# connect-ino.net
KiCad netlist of a schematic drawn in EAGLE
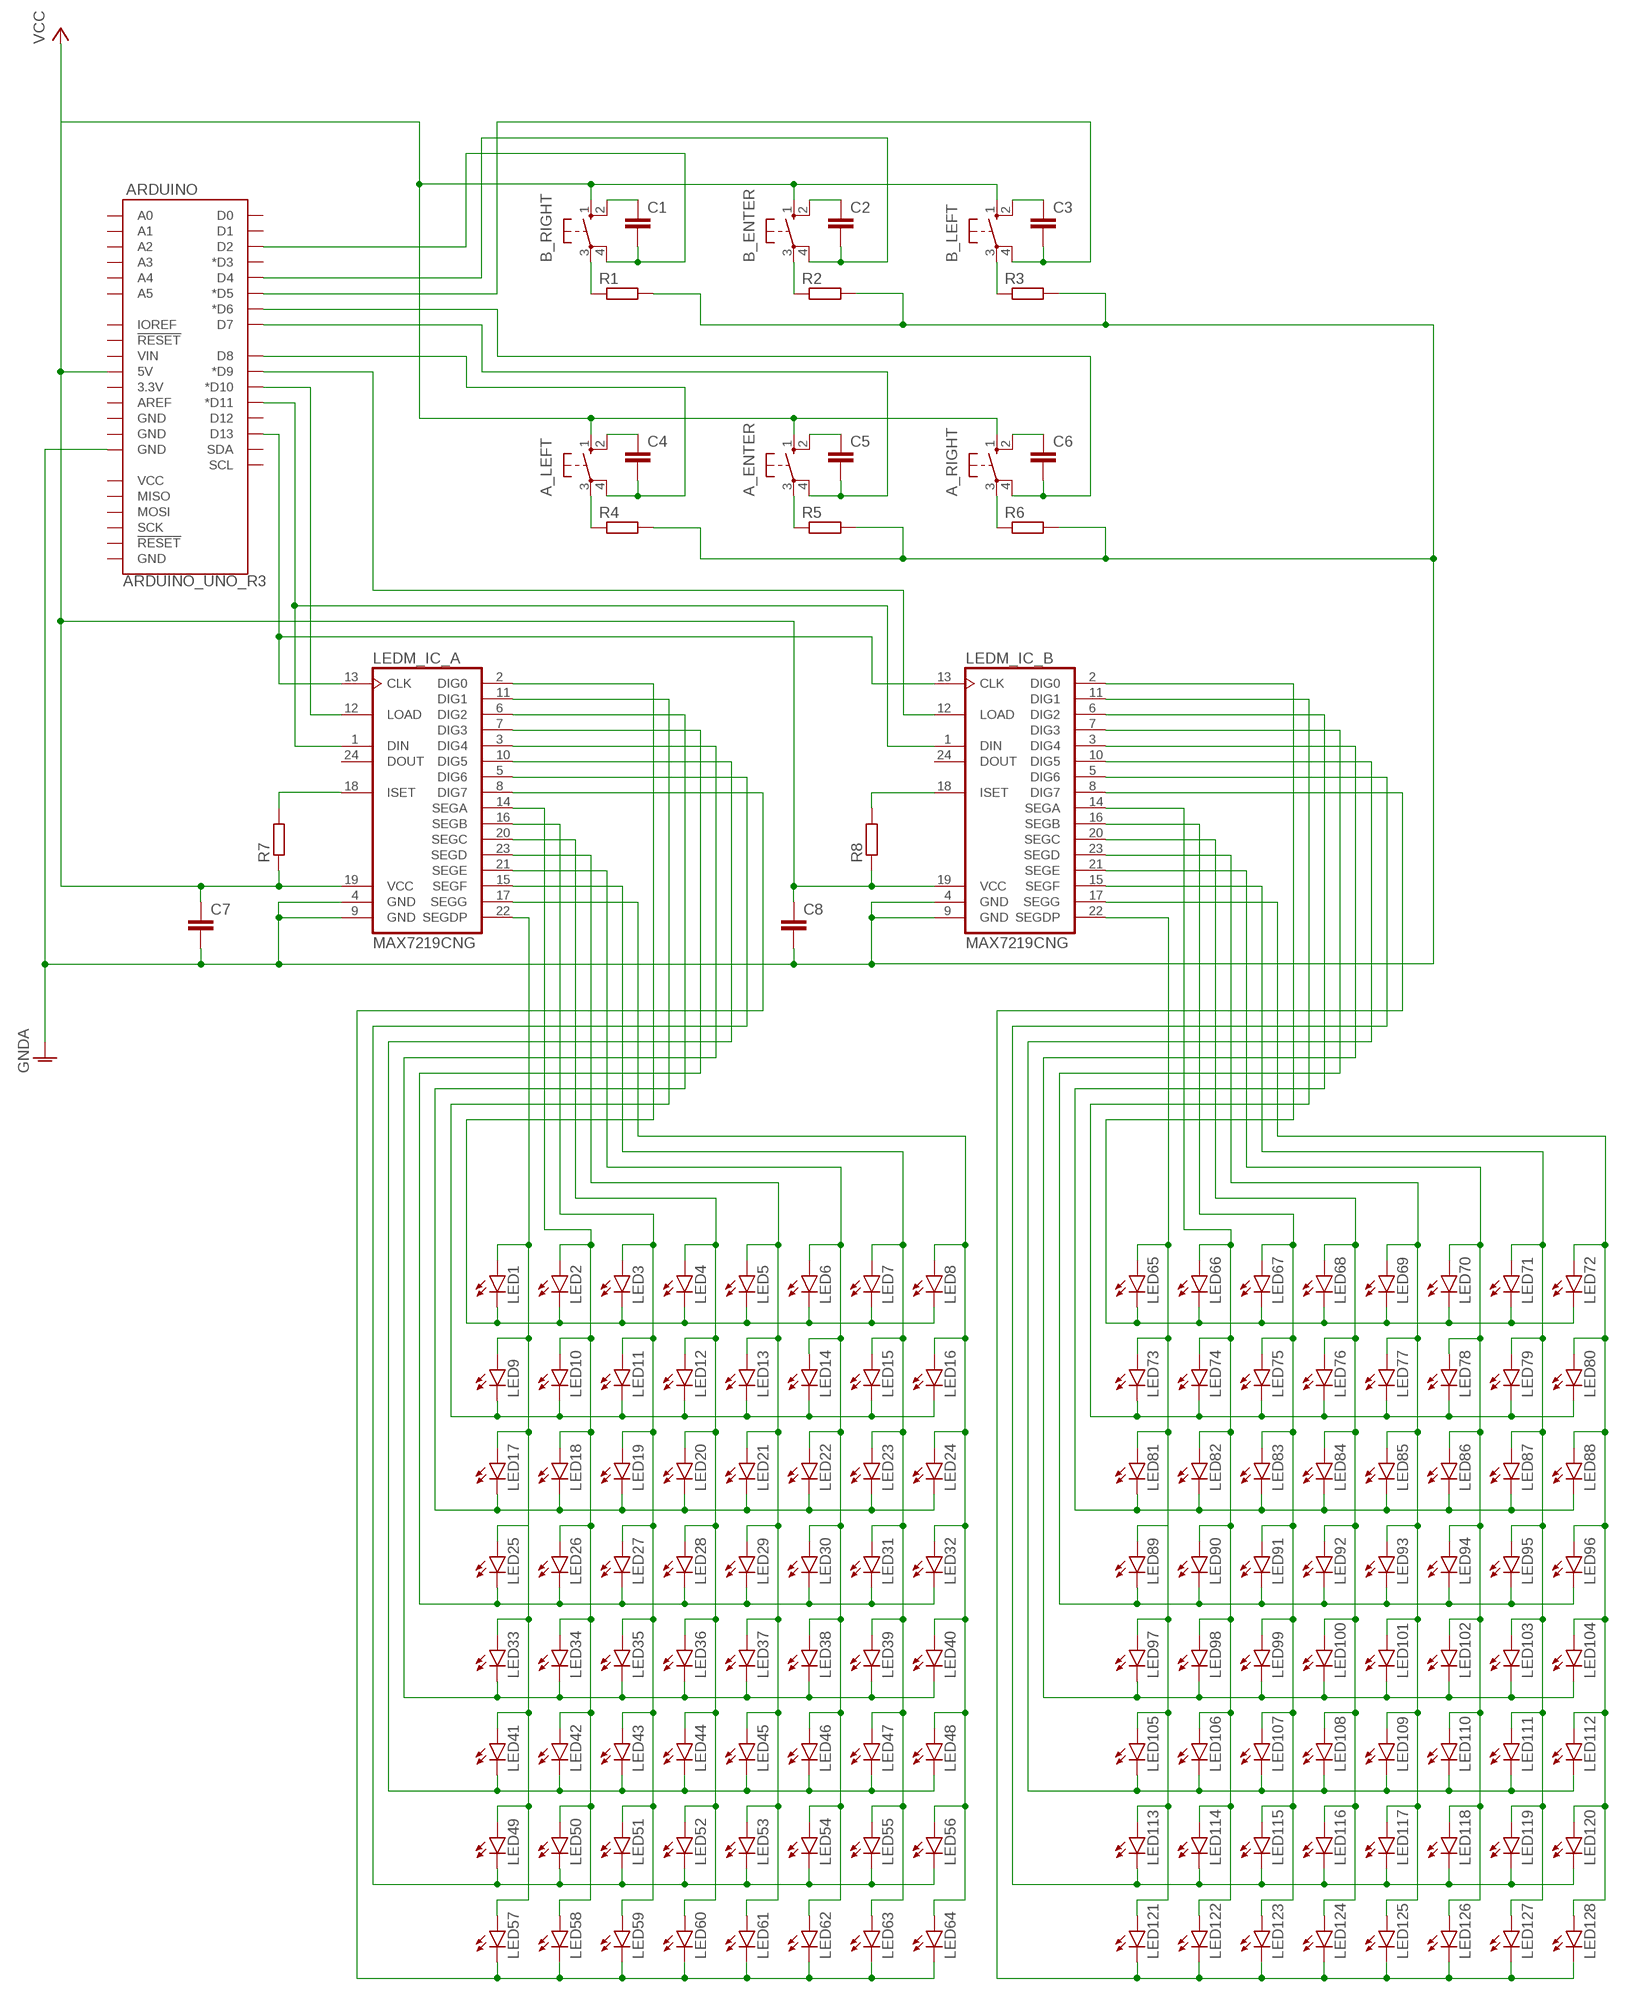
[diagram p0: schematic, sheet 1]

(export (version "E")
  (design (tool "Eeschema 10.0.6"))
  (components
    (comp (ref "ARDUINO")
      (value "ARDUINO_UNO_R3")
      (footprint "eagle-import:ARDUINO_R3")
      (libsource (lib "eagle-import") (part "ARDUINO_UNO_R3"))
    )
    (comp (ref "A_ENTER")
      (value "10-XX")
      (footprint "eagle-import:B3F-10XX")
      (fields (field (name "MPN") "B3F-1000"))
      (libsource (lib "eagle-import") (part "10-XX"))
    )
    (comp (ref "A_LEFT")
      (value "10-XX")
      (footprint "eagle-import:B3F-10XX")
      (fields (field (name "MPN") "B3F-1000"))
      (libsource (lib "eagle-import") (part "10-XX"))
    )
    (comp (ref "A_RIGHT")
      (value "10-XX")
      (footprint "eagle-import:B3F-10XX")
      (fields (field (name "MPN") "B3F-1000"))
      (libsource (lib "eagle-import") (part "10-XX"))
    )
    (comp (ref "B_ENTER")
      (value "10-XX")
      (footprint "eagle-import:B3F-10XX")
      (fields (field (name "MPN") "B3F-1000"))
      (libsource (lib "eagle-import") (part "10-XX"))
    )
    (comp (ref "B_LEFT")
      (value "10-XX")
      (footprint "eagle-import:B3F-10XX")
      (fields (field (name "MPN") "B3F-1000"))
      (libsource (lib "eagle-import") (part "10-XX"))
    )
    (comp (ref "B_RIGHT")
      (value "10-XX")
      (footprint "eagle-import:B3F-10XX")
      (fields (field (name "MPN") "B3F-1000"))
      (libsource (lib "eagle-import") (part "10-XX"))
    )
    (comp (ref "C1")
      (value "C2,5-3")
      (footprint "eagle-import:C2.5-3")
      (libsource (lib "eagle-import") (part "C2,5-3"))
    )
    (comp (ref "C2")
      (value "C2,5-3")
      (footprint "eagle-import:C2.5-3")
      (libsource (lib "eagle-import") (part "C2,5-3"))
    )
    (comp (ref "C3")
      (value "C2,5-3")
      (footprint "eagle-import:C2.5-3")
      (libsource (lib "eagle-import") (part "C2,5-3"))
    )
    (comp (ref "C4")
      (value "C2,5-3")
      (footprint "eagle-import:C2.5-3")
      (libsource (lib "eagle-import") (part "C2,5-3"))
    )
    (comp (ref "C5")
      (value "C2,5-3")
      (footprint "eagle-import:C2.5-3")
      (libsource (lib "eagle-import") (part "C2,5-3"))
    )
    (comp (ref "C6")
      (value "C2,5-3")
      (footprint "eagle-import:C2.5-3")
      (libsource (lib "eagle-import") (part "C2,5-3"))
    )
    (comp (ref "C7")
      (value "C2,5-3")
      (footprint "eagle-import:C2.5-3")
      (libsource (lib "eagle-import") (part "C2,5-3"))
    )
    (comp (ref "C8")
      (value "C2,5-3")
      (footprint "eagle-import:C2.5-3")
      (libsource (lib "eagle-import") (part "C2,5-3"))
    )
    (comp (ref "LED1")
      (value "LAP4-BOTTOM")
      (footprint "eagle-import:P47F-BOTTOM")
      (libsource (lib "eagle-import") (part "P4-BOTTOMLA"))
    )
    (comp (ref "LED2")
      (value "LAP4-BOTTOM")
      (footprint "eagle-import:P47F-BOTTOM")
      (libsource (lib "eagle-import") (part "P4-BOTTOMLA"))
    )
    (comp (ref "LED3")
      (value "LAP4-BOTTOM")
      (footprint "eagle-import:P47F-BOTTOM")
      (libsource (lib "eagle-import") (part "P4-BOTTOMLA"))
    )
    (comp (ref "LED4")
      (value "LAP4-BOTTOM")
      (footprint "eagle-import:P47F-BOTTOM")
      (libsource (lib "eagle-import") (part "P4-BOTTOMLA"))
    )
    (comp (ref "LED5")
      (value "LAP4-BOTTOM")
      (footprint "eagle-import:P47F-BOTTOM")
      (libsource (lib "eagle-import") (part "P4-BOTTOMLA"))
    )
    (comp (ref "LED6")
      (value "LAP4-BOTTOM")
      (footprint "eagle-import:P47F-BOTTOM")
      (libsource (lib "eagle-import") (part "P4-BOTTOMLA"))
    )
    (comp (ref "LED7")
      (value "LAP4-BOTTOM")
      (footprint "eagle-import:P47F-BOTTOM")
      (libsource (lib "eagle-import") (part "P4-BOTTOMLA"))
    )
    (comp (ref "LED8")
      (value "LAP4-BOTTOM")
      (footprint "eagle-import:P47F-BOTTOM")
      (libsource (lib "eagle-import") (part "P4-BOTTOMLA"))
    )
    (comp (ref "LED9")
      (value "LAP4-BOTTOM")
      (footprint "eagle-import:P47F-BOTTOM")
      (libsource (lib "eagle-import") (part "P4-BOTTOMLA"))
    )
    (comp (ref "LED10")
      (value "LAP4-BOTTOM")
      (footprint "eagle-import:P47F-BOTTOM")
      (libsource (lib "eagle-import") (part "P4-BOTTOMLA"))
    )
    (comp (ref "LED11")
      (value "LAP4-BOTTOM")
      (footprint "eagle-import:P47F-BOTTOM")
      (libsource (lib "eagle-import") (part "P4-BOTTOMLA"))
    )
    (comp (ref "LED12")
      (value "LAP4-BOTTOM")
      (footprint "eagle-import:P47F-BOTTOM")
      (libsource (lib "eagle-import") (part "P4-BOTTOMLA"))
    )
    (comp (ref "LED13")
      (value "LAP4-BOTTOM")
      (footprint "eagle-import:P47F-BOTTOM")
      (libsource (lib "eagle-import") (part "P4-BOTTOMLA"))
    )
    (comp (ref "LED14")
      (value "LAP4-BOTTOM")
      (footprint "eagle-import:P47F-BOTTOM")
      (libsource (lib "eagle-import") (part "P4-BOTTOMLA"))
    )
    (comp (ref "LED15")
      (value "LAP4-BOTTOM")
      (footprint "eagle-import:P47F-BOTTOM")
      (libsource (lib "eagle-import") (part "P4-BOTTOMLA"))
    )
    (comp (ref "LED16")
      (value "LAP4-BOTTOM")
      (footprint "eagle-import:P47F-BOTTOM")
      (libsource (lib "eagle-import") (part "P4-BOTTOMLA"))
    )
    (comp (ref "LED17")
      (value "LAP4-BOTTOM")
      (footprint "eagle-import:P47F-BOTTOM")
      (libsource (lib "eagle-import") (part "P4-BOTTOMLA"))
    )
    (comp (ref "LED18")
      (value "LAP4-BOTTOM")
      (footprint "eagle-import:P47F-BOTTOM")
      (libsource (lib "eagle-import") (part "P4-BOTTOMLA"))
    )
    (comp (ref "LED19")
      (value "LAP4-BOTTOM")
      (footprint "eagle-import:P47F-BOTTOM")
      (libsource (lib "eagle-import") (part "P4-BOTTOMLA"))
    )
    (comp (ref "LED20")
      (value "LAP4-BOTTOM")
      (footprint "eagle-import:P47F-BOTTOM")
      (libsource (lib "eagle-import") (part "P4-BOTTOMLA"))
    )
    (comp (ref "LED21")
      (value "LAP4-BOTTOM")
      (footprint "eagle-import:P47F-BOTTOM")
      (libsource (lib "eagle-import") (part "P4-BOTTOMLA"))
    )
    (comp (ref "LED22")
      (value "LAP4-BOTTOM")
      (footprint "eagle-import:P47F-BOTTOM")
      (libsource (lib "eagle-import") (part "P4-BOTTOMLA"))
    )
    (comp (ref "LED23")
      (value "LAP4-BOTTOM")
      (footprint "eagle-import:P47F-BOTTOM")
      (libsource (lib "eagle-import") (part "P4-BOTTOMLA"))
    )
    (comp (ref "LED24")
      (value "LAP4-BOTTOM")
      (footprint "eagle-import:P47F-BOTTOM")
      (libsource (lib "eagle-import") (part "P4-BOTTOMLA"))
    )
    (comp (ref "LED25")
      (value "LAP4-BOTTOM")
      (footprint "eagle-import:P47F-BOTTOM")
      (libsource (lib "eagle-import") (part "P4-BOTTOMLA"))
    )
    (comp (ref "LED26")
      (value "LAP4-BOTTOM")
      (footprint "eagle-import:P47F-BOTTOM")
      (libsource (lib "eagle-import") (part "P4-BOTTOMLA"))
    )
    (comp (ref "LED27")
      (value "LAP4-BOTTOM")
      (footprint "eagle-import:P47F-BOTTOM")
      (libsource (lib "eagle-import") (part "P4-BOTTOMLA"))
    )
    (comp (ref "LED28")
      (value "LAP4-BOTTOM")
      (footprint "eagle-import:P47F-BOTTOM")
      (libsource (lib "eagle-import") (part "P4-BOTTOMLA"))
    )
    (comp (ref "LED29")
      (value "LAP4-BOTTOM")
      (footprint "eagle-import:P47F-BOTTOM")
      (libsource (lib "eagle-import") (part "P4-BOTTOMLA"))
    )
    (comp (ref "LED30")
      (value "LAP4-BOTTOM")
      (footprint "eagle-import:P47F-BOTTOM")
      (libsource (lib "eagle-import") (part "P4-BOTTOMLA"))
    )
    (comp (ref "LED31")
      (value "LAP4-BOTTOM")
      (footprint "eagle-import:P47F-BOTTOM")
      (libsource (lib "eagle-import") (part "P4-BOTTOMLA"))
    )
    (comp (ref "LED32")
      (value "LAP4-BOTTOM")
      (footprint "eagle-import:P47F-BOTTOM")
      (libsource (lib "eagle-import") (part "P4-BOTTOMLA"))
    )
    (comp (ref "LED33")
      (value "LAP4-BOTTOM")
      (footprint "eagle-import:P47F-BOTTOM")
      (libsource (lib "eagle-import") (part "P4-BOTTOMLA"))
    )
    (comp (ref "LED34")
      (value "LAP4-BOTTOM")
      (footprint "eagle-import:P47F-BOTTOM")
      (libsource (lib "eagle-import") (part "P4-BOTTOMLA"))
    )
    (comp (ref "LED35")
      (value "LAP4-BOTTOM")
      (footprint "eagle-import:P47F-BOTTOM")
      (libsource (lib "eagle-import") (part "P4-BOTTOMLA"))
    )
    (comp (ref "LED36")
      (value "LAP4-BOTTOM")
      (footprint "eagle-import:P47F-BOTTOM")
      (libsource (lib "eagle-import") (part "P4-BOTTOMLA"))
    )
    (comp (ref "LED37")
      (value "LAP4-BOTTOM")
      (footprint "eagle-import:P47F-BOTTOM")
      (libsource (lib "eagle-import") (part "P4-BOTTOMLA"))
    )
    (comp (ref "LED38")
      (value "LAP4-BOTTOM")
      (footprint "eagle-import:P47F-BOTTOM")
      (libsource (lib "eagle-import") (part "P4-BOTTOMLA"))
    )
    (comp (ref "LED39")
      (value "LAP4-BOTTOM")
      (footprint "eagle-import:P47F-BOTTOM")
      (libsource (lib "eagle-import") (part "P4-BOTTOMLA"))
    )
    (comp (ref "LED40")
      (value "LAP4-BOTTOM")
      (footprint "eagle-import:P47F-BOTTOM")
      (libsource (lib "eagle-import") (part "P4-BOTTOMLA"))
    )
    (comp (ref "LED41")
      (value "LAP4-BOTTOM")
      (footprint "eagle-import:P47F-BOTTOM")
      (libsource (lib "eagle-import") (part "P4-BOTTOMLA"))
    )
    (comp (ref "LED42")
      (value "LAP4-BOTTOM")
      (footprint "eagle-import:P47F-BOTTOM")
      (libsource (lib "eagle-import") (part "P4-BOTTOMLA"))
    )
    (comp (ref "LED43")
      (value "LAP4-BOTTOM")
      (footprint "eagle-import:P47F-BOTTOM")
      (libsource (lib "eagle-import") (part "P4-BOTTOMLA"))
    )
    (comp (ref "LED44")
      (value "LAP4-BOTTOM")
      (footprint "eagle-import:P47F-BOTTOM")
      (libsource (lib "eagle-import") (part "P4-BOTTOMLA"))
    )
    (comp (ref "LED45")
      (value "LAP4-BOTTOM")
      (footprint "eagle-import:P47F-BOTTOM")
      (libsource (lib "eagle-import") (part "P4-BOTTOMLA"))
    )
    (comp (ref "LED46")
      (value "LAP4-BOTTOM")
      (footprint "eagle-import:P47F-BOTTOM")
      (libsource (lib "eagle-import") (part "P4-BOTTOMLA"))
    )
    (comp (ref "LED47")
      (value "LAP4-BOTTOM")
      (footprint "eagle-import:P47F-BOTTOM")
      (libsource (lib "eagle-import") (part "P4-BOTTOMLA"))
    )
    (comp (ref "LED48")
      (value "LAP4-BOTTOM")
      (footprint "eagle-import:P47F-BOTTOM")
      (libsource (lib "eagle-import") (part "P4-BOTTOMLA"))
    )
    (comp (ref "LED49")
      (value "LAP4-BOTTOM")
      (footprint "eagle-import:P47F-BOTTOM")
      (libsource (lib "eagle-import") (part "P4-BOTTOMLA"))
    )
    (comp (ref "LED50")
      (value "LAP4-BOTTOM")
      (footprint "eagle-import:P47F-BOTTOM")
      (libsource (lib "eagle-import") (part "P4-BOTTOMLA"))
    )
    (comp (ref "LED51")
      (value "LAP4-BOTTOM")
      (footprint "eagle-import:P47F-BOTTOM")
      (libsource (lib "eagle-import") (part "P4-BOTTOMLA"))
    )
    (comp (ref "LED52")
      (value "LAP4-BOTTOM")
      (footprint "eagle-import:P47F-BOTTOM")
      (libsource (lib "eagle-import") (part "P4-BOTTOMLA"))
    )
    (comp (ref "LED53")
      (value "LAP4-BOTTOM")
      (footprint "eagle-import:P47F-BOTTOM")
      (libsource (lib "eagle-import") (part "P4-BOTTOMLA"))
    )
    (comp (ref "LED54")
      (value "LAP4-BOTTOM")
      (footprint "eagle-import:P47F-BOTTOM")
      (libsource (lib "eagle-import") (part "P4-BOTTOMLA"))
    )
    (comp (ref "LED55")
      (value "LAP4-BOTTOM")
      (footprint "eagle-import:P47F-BOTTOM")
      (libsource (lib "eagle-import") (part "P4-BOTTOMLA"))
    )
    (comp (ref "LED56")
      (value "LAP4-BOTTOM")
      (footprint "eagle-import:P47F-BOTTOM")
      (libsource (lib "eagle-import") (part "P4-BOTTOMLA"))
    )
    (comp (ref "LED57")
      (value "LAP4-BOTTOM")
      (footprint "eagle-import:P47F-BOTTOM")
      (libsource (lib "eagle-import") (part "P4-BOTTOMLA"))
    )
    (comp (ref "LED58")
      (value "LAP4-BOTTOM")
      (footprint "eagle-import:P47F-BOTTOM")
      (libsource (lib "eagle-import") (part "P4-BOTTOMLA"))
    )
    (comp (ref "LED59")
      (value "LAP4-BOTTOM")
      (footprint "eagle-import:P47F-BOTTOM")
      (libsource (lib "eagle-import") (part "P4-BOTTOMLA"))
    )
    (comp (ref "LED60")
      (value "LAP4-BOTTOM")
      (footprint "eagle-import:P47F-BOTTOM")
      (libsource (lib "eagle-import") (part "P4-BOTTOMLA"))
    )
    (comp (ref "LED61")
      (value "LAP4-BOTTOM")
      (footprint "eagle-import:P47F-BOTTOM")
      (libsource (lib "eagle-import") (part "P4-BOTTOMLA"))
    )
    (comp (ref "LED62")
      (value "LAP4-BOTTOM")
      (footprint "eagle-import:P47F-BOTTOM")
      (libsource (lib "eagle-import") (part "P4-BOTTOMLA"))
    )
    (comp (ref "LED63")
      (value "LAP4-BOTTOM")
      (footprint "eagle-import:P47F-BOTTOM")
      (libsource (lib "eagle-import") (part "P4-BOTTOMLA"))
    )
    (comp (ref "LED64")
      (value "LAP4-BOTTOM")
      (footprint "eagle-import:P47F-BOTTOM")
      (libsource (lib "eagle-import") (part "P4-BOTTOMLA"))
    )
    (comp (ref "LED65")
      (value "LAP4-BOTTOM")
      (footprint "eagle-import:P47F-BOTTOM")
      (libsource (lib "eagle-import") (part "P4-BOTTOMLA"))
    )
    (comp (ref "LED66")
      (value "LAP4-BOTTOM")
      (footprint "eagle-import:P47F-BOTTOM")
      (libsource (lib "eagle-import") (part "P4-BOTTOMLA"))
    )
    (comp (ref "LED67")
      (value "LAP4-BOTTOM")
      (footprint "eagle-import:P47F-BOTTOM")
      (libsource (lib "eagle-import") (part "P4-BOTTOMLA"))
    )
    (comp (ref "LED68")
      (value "LAP4-BOTTOM")
      (footprint "eagle-import:P47F-BOTTOM")
      (libsource (lib "eagle-import") (part "P4-BOTTOMLA"))
    )
    (comp (ref "LED69")
      (value "LAP4-BOTTOM")
      (footprint "eagle-import:P47F-BOTTOM")
      (libsource (lib "eagle-import") (part "P4-BOTTOMLA"))
    )
    (comp (ref "LED70")
      (value "LAP4-BOTTOM")
      (footprint "eagle-import:P47F-BOTTOM")
      (libsource (lib "eagle-import") (part "P4-BOTTOMLA"))
    )
    (comp (ref "LED71")
      (value "LAP4-BOTTOM")
      (footprint "eagle-import:P47F-BOTTOM")
      (libsource (lib "eagle-import") (part "P4-BOTTOMLA"))
    )
    (comp (ref "LED72")
      (value "LAP4-BOTTOM")
      (footprint "eagle-import:P47F-BOTTOM")
      (libsource (lib "eagle-import") (part "P4-BOTTOMLA"))
    )
    (comp (ref "LED73")
      (value "LAP4-BOTTOM")
      (footprint "eagle-import:P47F-BOTTOM")
      (libsource (lib "eagle-import") (part "P4-BOTTOMLA"))
    )
    (comp (ref "LED74")
      (value "LAP4-BOTTOM")
      (footprint "eagle-import:P47F-BOTTOM")
      (libsource (lib "eagle-import") (part "P4-BOTTOMLA"))
    )
    (comp (ref "LED75")
      (value "LAP4-BOTTOM")
      (footprint "eagle-import:P47F-BOTTOM")
      (libsource (lib "eagle-import") (part "P4-BOTTOMLA"))
    )
    (comp (ref "LED76")
      (value "LAP4-BOTTOM")
      (footprint "eagle-import:P47F-BOTTOM")
      (libsource (lib "eagle-import") (part "P4-BOTTOMLA"))
    )
    (comp (ref "LED77")
      (value "LAP4-BOTTOM")
      (footprint "eagle-import:P47F-BOTTOM")
      (libsource (lib "eagle-import") (part "P4-BOTTOMLA"))
    )
    (comp (ref "LED78")
      (value "LAP4-BOTTOM")
      (footprint "eagle-import:P47F-BOTTOM")
      (libsource (lib "eagle-import") (part "P4-BOTTOMLA"))
    )
    (comp (ref "LED79")
      (value "LAP4-BOTTOM")
      (footprint "eagle-import:P47F-BOTTOM")
      (libsource (lib "eagle-import") (part "P4-BOTTOMLA"))
    )
    (comp (ref "LED80")
      (value "LAP4-BOTTOM")
      (footprint "eagle-import:P47F-BOTTOM")
      (libsource (lib "eagle-import") (part "P4-BOTTOMLA"))
    )
    (comp (ref "LED81")
      (value "LAP4-BOTTOM")
      (footprint "eagle-import:P47F-BOTTOM")
      (libsource (lib "eagle-import") (part "P4-BOTTOMLA"))
    )
    (comp (ref "LED82")
      (value "LAP4-BOTTOM")
      (footprint "eagle-import:P47F-BOTTOM")
      (libsource (lib "eagle-import") (part "P4-BOTTOMLA"))
    )
    (comp (ref "LED83")
      (value "LAP4-BOTTOM")
      (footprint "eagle-import:P47F-BOTTOM")
      (libsource (lib "eagle-import") (part "P4-BOTTOMLA"))
    )
    (comp (ref "LED84")
      (value "LAP4-BOTTOM")
      (footprint "eagle-import:P47F-BOTTOM")
      (libsource (lib "eagle-import") (part "P4-BOTTOMLA"))
    )
    (comp (ref "LED85")
      (value "LAP4-BOTTOM")
      (footprint "eagle-import:P47F-BOTTOM")
      (libsource (lib "eagle-import") (part "P4-BOTTOMLA"))
    )
    (comp (ref "LED86")
      (value "LAP4-BOTTOM")
      (footprint "eagle-import:P47F-BOTTOM")
      (libsource (lib "eagle-import") (part "P4-BOTTOMLA"))
    )
    (comp (ref "LED87")
      (value "LAP4-BOTTOM")
      (footprint "eagle-import:P47F-BOTTOM")
      (libsource (lib "eagle-import") (part "P4-BOTTOMLA"))
    )
    (comp (ref "LED88")
      (value "LAP4-BOTTOM")
      (footprint "eagle-import:P47F-BOTTOM")
      (libsource (lib "eagle-import") (part "P4-BOTTOMLA"))
    )
    (comp (ref "LED89")
      (value "LAP4-BOTTOM")
      (footprint "eagle-import:P47F-BOTTOM")
      (libsource (lib "eagle-import") (part "P4-BOTTOMLA"))
    )
    (comp (ref "LED90")
      (value "LAP4-BOTTOM")
      (footprint "eagle-import:P47F-BOTTOM")
      (libsource (lib "eagle-import") (part "P4-BOTTOMLA"))
    )
    (comp (ref "LED91")
      (value "LAP4-BOTTOM")
      (footprint "eagle-import:P47F-BOTTOM")
      (libsource (lib "eagle-import") (part "P4-BOTTOMLA"))
    )
    (comp (ref "LED92")
      (value "LAP4-BOTTOM")
      (footprint "eagle-import:P47F-BOTTOM")
      (libsource (lib "eagle-import") (part "P4-BOTTOMLA"))
    )
    (comp (ref "LED93")
      (value "LAP4-BOTTOM")
      (footprint "eagle-import:P47F-BOTTOM")
      (libsource (lib "eagle-import") (part "P4-BOTTOMLA"))
    )
    (comp (ref "LED94")
      (value "LAP4-BOTTOM")
      (footprint "eagle-import:P47F-BOTTOM")
      (libsource (lib "eagle-import") (part "P4-BOTTOMLA"))
    )
    (comp (ref "LED95")
      (value "LAP4-BOTTOM")
      (footprint "eagle-import:P47F-BOTTOM")
      (libsource (lib "eagle-import") (part "P4-BOTTOMLA"))
    )
    (comp (ref "LED96")
      (value "LAP4-BOTTOM")
      (footprint "eagle-import:P47F-BOTTOM")
      (libsource (lib "eagle-import") (part "P4-BOTTOMLA"))
    )
    (comp (ref "LED97")
      (value "LAP4-BOTTOM")
      (footprint "eagle-import:P47F-BOTTOM")
      (libsource (lib "eagle-import") (part "P4-BOTTOMLA"))
    )
    (comp (ref "LED98")
      (value "LAP4-BOTTOM")
      (footprint "eagle-import:P47F-BOTTOM")
      (libsource (lib "eagle-import") (part "P4-BOTTOMLA"))
    )
    (comp (ref "LED99")
      (value "LAP4-BOTTOM")
      (footprint "eagle-import:P47F-BOTTOM")
      (libsource (lib "eagle-import") (part "P4-BOTTOMLA"))
    )
    (comp (ref "LED100")
      (value "LAP4-BOTTOM")
      (footprint "eagle-import:P47F-BOTTOM")
      (libsource (lib "eagle-import") (part "P4-BOTTOMLA"))
    )
    (comp (ref "LED101")
      (value "LAP4-BOTTOM")
      (footprint "eagle-import:P47F-BOTTOM")
      (libsource (lib "eagle-import") (part "P4-BOTTOMLA"))
    )
    (comp (ref "LED102")
      (value "LAP4-BOTTOM")
      (footprint "eagle-import:P47F-BOTTOM")
      (libsource (lib "eagle-import") (part "P4-BOTTOMLA"))
    )
    (comp (ref "LED103")
      (value "LAP4-BOTTOM")
      (footprint "eagle-import:P47F-BOTTOM")
      (libsource (lib "eagle-import") (part "P4-BOTTOMLA"))
    )
    (comp (ref "LED104")
      (value "LAP4-BOTTOM")
      (footprint "eagle-import:P47F-BOTTOM")
      (libsource (lib "eagle-import") (part "P4-BOTTOMLA"))
    )
    (comp (ref "LED105")
      (value "LAP4-BOTTOM")
      (footprint "eagle-import:P47F-BOTTOM")
      (libsource (lib "eagle-import") (part "P4-BOTTOMLA"))
    )
    (comp (ref "LED106")
      (value "LAP4-BOTTOM")
      (footprint "eagle-import:P47F-BOTTOM")
      (libsource (lib "eagle-import") (part "P4-BOTTOMLA"))
    )
    (comp (ref "LED107")
      (value "LAP4-BOTTOM")
      (footprint "eagle-import:P47F-BOTTOM")
      (libsource (lib "eagle-import") (part "P4-BOTTOMLA"))
    )
    (comp (ref "LED108")
      (value "LAP4-BOTTOM")
      (footprint "eagle-import:P47F-BOTTOM")
      (libsource (lib "eagle-import") (part "P4-BOTTOMLA"))
    )
    (comp (ref "LED109")
      (value "LAP4-BOTTOM")
      (footprint "eagle-import:P47F-BOTTOM")
      (libsource (lib "eagle-import") (part "P4-BOTTOMLA"))
    )
    (comp (ref "LED110")
      (value "LAP4-BOTTOM")
      (footprint "eagle-import:P47F-BOTTOM")
      (libsource (lib "eagle-import") (part "P4-BOTTOMLA"))
    )
    (comp (ref "LED111")
      (value "LAP4-BOTTOM")
      (footprint "eagle-import:P47F-BOTTOM")
      (libsource (lib "eagle-import") (part "P4-BOTTOMLA"))
    )
    (comp (ref "LED112")
      (value "LAP4-BOTTOM")
      (footprint "eagle-import:P47F-BOTTOM")
      (libsource (lib "eagle-import") (part "P4-BOTTOMLA"))
    )
    (comp (ref "LED113")
      (value "LAP4-BOTTOM")
      (footprint "eagle-import:P47F-BOTTOM")
      (libsource (lib "eagle-import") (part "P4-BOTTOMLA"))
    )
    (comp (ref "LED114")
      (value "LAP4-BOTTOM")
      (footprint "eagle-import:P47F-BOTTOM")
      (libsource (lib "eagle-import") (part "P4-BOTTOMLA"))
    )
    (comp (ref "LED115")
      (value "LAP4-BOTTOM")
      (footprint "eagle-import:P47F-BOTTOM")
      (libsource (lib "eagle-import") (part "P4-BOTTOMLA"))
    )
    (comp (ref "LED116")
      (value "LAP4-BOTTOM")
      (footprint "eagle-import:P47F-BOTTOM")
      (libsource (lib "eagle-import") (part "P4-BOTTOMLA"))
    )
    (comp (ref "LED117")
      (value "LAP4-BOTTOM")
      (footprint "eagle-import:P47F-BOTTOM")
      (libsource (lib "eagle-import") (part "P4-BOTTOMLA"))
    )
    (comp (ref "LED118")
      (value "LAP4-BOTTOM")
      (footprint "eagle-import:P47F-BOTTOM")
      (libsource (lib "eagle-import") (part "P4-BOTTOMLA"))
    )
    (comp (ref "LED119")
      (value "LAP4-BOTTOM")
      (footprint "eagle-import:P47F-BOTTOM")
      (libsource (lib "eagle-import") (part "P4-BOTTOMLA"))
    )
    (comp (ref "LED120")
      (value "LAP4-BOTTOM")
      (footprint "eagle-import:P47F-BOTTOM")
      (libsource (lib "eagle-import") (part "P4-BOTTOMLA"))
    )
    (comp (ref "LED121")
      (value "LAP4-BOTTOM")
      (footprint "eagle-import:P47F-BOTTOM")
      (libsource (lib "eagle-import") (part "P4-BOTTOMLA"))
    )
    (comp (ref "LED122")
      (value "LAP4-BOTTOM")
      (footprint "eagle-import:P47F-BOTTOM")
      (libsource (lib "eagle-import") (part "P4-BOTTOMLA"))
    )
    (comp (ref "LED123")
      (value "LAP4-BOTTOM")
      (footprint "eagle-import:P47F-BOTTOM")
      (libsource (lib "eagle-import") (part "P4-BOTTOMLA"))
    )
    (comp (ref "LED124")
      (value "LAP4-BOTTOM")
      (footprint "eagle-import:P47F-BOTTOM")
      (libsource (lib "eagle-import") (part "P4-BOTTOMLA"))
    )
    (comp (ref "LED125")
      (value "LAP4-BOTTOM")
      (footprint "eagle-import:P47F-BOTTOM")
      (libsource (lib "eagle-import") (part "P4-BOTTOMLA"))
    )
    (comp (ref "LED126")
      (value "LAP4-BOTTOM")
      (footprint "eagle-import:P47F-BOTTOM")
      (libsource (lib "eagle-import") (part "P4-BOTTOMLA"))
    )
    (comp (ref "LED127")
      (value "LAP4-BOTTOM")
      (footprint "eagle-import:P47F-BOTTOM")
      (libsource (lib "eagle-import") (part "P4-BOTTOMLA"))
    )
    (comp (ref "LED128")
      (value "LAP4-BOTTOM")
      (footprint "eagle-import:P47F-BOTTOM")
      (libsource (lib "eagle-import") (part "P4-BOTTOMLA"))
    )
    (comp (ref "LEDM_IC_A")
      (value "MAX7219CNG")
      (footprint "eagle-import:DIL24-3")
      (fields (field (name "MF") "MAXIM"))
      (libsource (lib "eagle-import") (part "MAX7219CNG"))
    )
    (comp (ref "LEDM_IC_B")
      (value "MAX7219CNG")
      (footprint "eagle-import:DIL24-3")
      (fields (field (name "MF") "MAXIM"))
      (libsource (lib "eagle-import") (part "MAX7219CNG"))
    )
    (comp (ref "R1")
      (value "R-EU_0204/2V")
      (footprint "eagle-import:0204V")
      (libsource (lib "eagle-import") (part "R-EU_0204/2V"))
    )
    (comp (ref "R2")
      (value "R-EU_0204/2V")
      (footprint "eagle-import:0204V")
      (libsource (lib "eagle-import") (part "R-EU_0204/2V"))
    )
    (comp (ref "R3")
      (value "R-EU_0204/2V")
      (footprint "eagle-import:0204V")
      (libsource (lib "eagle-import") (part "R-EU_0204/2V"))
    )
    (comp (ref "R4")
      (value "R-EU_0204/2V")
      (footprint "eagle-import:0204V")
      (libsource (lib "eagle-import") (part "R-EU_0204/2V"))
    )
    (comp (ref "R5")
      (value "R-EU_0204/2V")
      (footprint "eagle-import:0204V")
      (libsource (lib "eagle-import") (part "R-EU_0204/2V"))
    )
    (comp (ref "R6")
      (value "R-EU_0204/2V")
      (footprint "eagle-import:0204V")
      (libsource (lib "eagle-import") (part "R-EU_0204/2V"))
    )
    (comp (ref "R7")
      (value "R-EU_0204/2V")
      (footprint "eagle-import:0204V")
      (libsource (lib "eagle-import") (part "R-EU_0204/2V"))
    )
    (comp (ref "R8")
      (value "R-EU_0204/2V")
      (footprint "eagle-import:0204V")
      (libsource (lib "eagle-import") (part "R-EU_0204/2V"))
    )
  )
  (nets
    (net (code "1") (name "GNDA") (class "Default")
      (node (ref "ARDUINO") (pin "GND@2") (pinfunction "GND_GND@2") (pintype "bidirectional"))
      (node (ref "C7") (pin "2") (pinfunction "2_2") (pintype "passive"))
      (node (ref "C8") (pin "2") (pinfunction "2_2") (pintype "passive"))
      (node (ref "LEDM_IC_A") (pin "4") (pinfunction "GND_4") (pintype "power_in"))
      (node (ref "LEDM_IC_A") (pin "9") (pinfunction "GND_9") (pintype "power_in"))
      (node (ref "LEDM_IC_B") (pin "4") (pinfunction "GND_4") (pintype "power_in"))
      (node (ref "LEDM_IC_B") (pin "9") (pinfunction "GND_9") (pintype "power_in"))
      (node (ref "R1") (pin "2") (pinfunction "2_2") (pintype "passive"))
      (node (ref "R2") (pin "2") (pinfunction "2_2") (pintype "passive"))
      (node (ref "R3") (pin "2") (pinfunction "2_2") (pintype "passive"))
      (node (ref "R4") (pin "2") (pinfunction "2_2") (pintype "passive"))
      (node (ref "R5") (pin "2") (pinfunction "2_2") (pintype "passive"))
      (node (ref "R6") (pin "2") (pinfunction "2_2") (pintype "passive"))
    )
    (net (code "2") (name "Net-(ARDUINO-*D5)") (class "Default")
      (node (ref "ARDUINO") (pin "D5") (pinfunction "*D5_D5") (pintype "bidirectional"))
      (node (ref "B_LEFT") (pin "4") (pinfunction "P1_4") (pintype "passive"))
      (node (ref "C3") (pin "2") (pinfunction "2_2") (pintype "passive"))
    )
    (net (code "3") (name "Net-(ARDUINO-*D6)") (class "Default")
      (node (ref "ARDUINO") (pin "D6") (pinfunction "*D6_D6") (pintype "bidirectional"))
      (node (ref "A_RIGHT") (pin "4") (pinfunction "P1_4") (pintype "passive"))
      (node (ref "C6") (pin "2") (pinfunction "2_2") (pintype "passive"))
    )
    (net (code "4") (name "Net-(ARDUINO-*D9)") (class "Default")
      (node (ref "ARDUINO") (pin "D9") (pinfunction "*D9_D9") (pintype "bidirectional"))
      (node (ref "LEDM_IC_B") (pin "12") (pinfunction "LOAD_12") (pintype "input"))
    )
    (net (code "5") (name "Net-(ARDUINO-*D10)") (class "Default")
      (node (ref "ARDUINO") (pin "D10") (pinfunction "*D10_D10") (pintype "bidirectional"))
      (node (ref "LEDM_IC_A") (pin "12") (pinfunction "LOAD_12") (pintype "input"))
    )
    (net (code "6") (name "Net-(ARDUINO-*D11)") (class "Default")
      (node (ref "ARDUINO") (pin "D11") (pinfunction "*D11_D11") (pintype "bidirectional"))
      (node (ref "LEDM_IC_A") (pin "1") (pinfunction "DIN_1") (pintype "input"))
      (node (ref "LEDM_IC_B") (pin "1") (pinfunction "DIN_1") (pintype "input"))
    )
    (net (code "7") (name "Net-(A_ENTER-P)") (class "Default")
      (node (ref "A_ENTER") (pin "3") (pinfunction "P_3") (pintype "passive"))
      (node (ref "R5") (pin "1") (pinfunction "1_1") (pintype "passive"))
    )
    (net (code "8") (name "Net-(A_ENTER-P1)") (class "Default")
      (node (ref "ARDUINO") (pin "D7") (pinfunction "D7_D7") (pintype "bidirectional"))
      (node (ref "A_ENTER") (pin "4") (pinfunction "P1_4") (pintype "passive"))
      (node (ref "C5") (pin "2") (pinfunction "2_2") (pintype "passive"))
    )
    (net (code "9") (name "Net-(A_ENTER-S1)") (class "Default")
      (node (ref "A_ENTER") (pin "2") (pinfunction "S1_2") (pintype "passive"))
      (node (ref "C5") (pin "1") (pinfunction "1_1") (pintype "passive"))
    )
    (net (code "10") (name "Net-(A_LEFT-P)") (class "Default")
      (node (ref "A_LEFT") (pin "3") (pinfunction "P_3") (pintype "passive"))
      (node (ref "R4") (pin "1") (pinfunction "1_1") (pintype "passive"))
    )
    (net (code "11") (name "Net-(A_LEFT-P1)") (class "Default")
      (node (ref "ARDUINO") (pin "D8") (pinfunction "D8_D8") (pintype "bidirectional"))
      (node (ref "A_LEFT") (pin "4") (pinfunction "P1_4") (pintype "passive"))
      (node (ref "C4") (pin "2") (pinfunction "2_2") (pintype "passive"))
    )
    (net (code "12") (name "Net-(A_LEFT-S1)") (class "Default")
      (node (ref "A_LEFT") (pin "2") (pinfunction "S1_2") (pintype "passive"))
      (node (ref "C4") (pin "1") (pinfunction "1_1") (pintype "passive"))
    )
    (net (code "13") (name "Net-(A_RIGHT-P)") (class "Default")
      (node (ref "A_RIGHT") (pin "3") (pinfunction "P_3") (pintype "passive"))
      (node (ref "R6") (pin "1") (pinfunction "1_1") (pintype "passive"))
    )
    (net (code "14") (name "Net-(A_RIGHT-S1)") (class "Default")
      (node (ref "A_RIGHT") (pin "2") (pinfunction "S1_2") (pintype "passive"))
      (node (ref "C6") (pin "1") (pinfunction "1_1") (pintype "passive"))
    )
    (net (code "15") (name "Net-(B_ENTER-P)") (class "Default")
      (node (ref "B_ENTER") (pin "3") (pinfunction "P_3") (pintype "passive"))
      (node (ref "R2") (pin "1") (pinfunction "1_1") (pintype "passive"))
    )
    (net (code "16") (name "Net-(B_ENTER-P1)") (class "Default")
      (node (ref "ARDUINO") (pin "D4") (pinfunction "D4_D4") (pintype "bidirectional"))
      (node (ref "B_ENTER") (pin "4") (pinfunction "P1_4") (pintype "passive"))
      (node (ref "C2") (pin "2") (pinfunction "2_2") (pintype "passive"))
    )
    (net (code "17") (name "Net-(B_ENTER-S1)") (class "Default")
      (node (ref "B_ENTER") (pin "2") (pinfunction "S1_2") (pintype "passive"))
      (node (ref "C2") (pin "1") (pinfunction "1_1") (pintype "passive"))
    )
    (net (code "18") (name "Net-(B_LEFT-P)") (class "Default")
      (node (ref "B_LEFT") (pin "3") (pinfunction "P_3") (pintype "passive"))
      (node (ref "R3") (pin "1") (pinfunction "1_1") (pintype "passive"))
    )
    (net (code "19") (name "Net-(B_LEFT-S1)") (class "Default")
      (node (ref "B_LEFT") (pin "2") (pinfunction "S1_2") (pintype "passive"))
      (node (ref "C3") (pin "1") (pinfunction "1_1") (pintype "passive"))
    )
    (net (code "20") (name "Net-(B_RIGHT-P)") (class "Default")
      (node (ref "B_RIGHT") (pin "3") (pinfunction "P_3") (pintype "passive"))
      (node (ref "R1") (pin "1") (pinfunction "1_1") (pintype "passive"))
    )
    (net (code "21") (name "Net-(B_RIGHT-P1)") (class "Default")
      (node (ref "ARDUINO") (pin "D2") (pinfunction "D2_D2") (pintype "bidirectional"))
      (node (ref "B_RIGHT") (pin "4") (pinfunction "P1_4") (pintype "passive"))
      (node (ref "C1") (pin "2") (pinfunction "2_2") (pintype "passive"))
    )
    (net (code "22") (name "Net-(B_RIGHT-S1)") (class "Default")
      (node (ref "B_RIGHT") (pin "2") (pinfunction "S1_2") (pintype "passive"))
      (node (ref "C1") (pin "1") (pinfunction "1_1") (pintype "passive"))
    )
    (net (code "23") (name "Net-(LEDM_IC_A-CLK)") (class "Default")
      (node (ref "ARDUINO") (pin "D13") (pinfunction "D13_D13") (pintype "bidirectional"))
      (node (ref "LEDM_IC_A") (pin "13") (pinfunction "CLK_13") (pintype "input"))
      (node (ref "LEDM_IC_B") (pin "13") (pinfunction "CLK_13") (pintype "input"))
    )
    (net (code "24") (name "Net-(LEDM_IC_A-DIG0)") (class "Default")
      (node (ref "LED1") (pin "C") (pinfunction "C_C") (pintype "passive"))
      (node (ref "LED2") (pin "C") (pinfunction "C_C") (pintype "passive"))
      (node (ref "LED3") (pin "C") (pinfunction "C_C") (pintype "passive"))
      (node (ref "LED4") (pin "C") (pinfunction "C_C") (pintype "passive"))
      (node (ref "LED5") (pin "C") (pinfunction "C_C") (pintype "passive"))
      (node (ref "LED6") (pin "C") (pinfunction "C_C") (pintype "passive"))
      (node (ref "LED7") (pin "C") (pinfunction "C_C") (pintype "passive"))
      (node (ref "LED8") (pin "C") (pinfunction "C_C") (pintype "passive"))
      (node (ref "LEDM_IC_A") (pin "2") (pinfunction "DIG0_2") (pintype "output"))
    )
    (net (code "25") (name "Net-(LEDM_IC_A-DIG1)") (class "Default")
      (node (ref "LED10") (pin "C") (pinfunction "C_C") (pintype "passive"))
      (node (ref "LED11") (pin "C") (pinfunction "C_C") (pintype "passive"))
      (node (ref "LED12") (pin "C") (pinfunction "C_C") (pintype "passive"))
      (node (ref "LED13") (pin "C") (pinfunction "C_C") (pintype "passive"))
      (node (ref "LED14") (pin "C") (pinfunction "C_C") (pintype "passive"))
      (node (ref "LED15") (pin "C") (pinfunction "C_C") (pintype "passive"))
      (node (ref "LED16") (pin "C") (pinfunction "C_C") (pintype "passive"))
      (node (ref "LED9") (pin "C") (pinfunction "C_C") (pintype "passive"))
      (node (ref "LEDM_IC_A") (pin "11") (pinfunction "DIG1_11") (pintype "output"))
    )
    (net (code "26") (name "Net-(LEDM_IC_A-DIG2)") (class "Default")
      (node (ref "LED17") (pin "C") (pinfunction "C_C") (pintype "passive"))
      (node (ref "LED18") (pin "C") (pinfunction "C_C") (pintype "passive"))
      (node (ref "LED19") (pin "C") (pinfunction "C_C") (pintype "passive"))
      (node (ref "LED20") (pin "C") (pinfunction "C_C") (pintype "passive"))
      (node (ref "LED21") (pin "C") (pinfunction "C_C") (pintype "passive"))
      (node (ref "LED22") (pin "C") (pinfunction "C_C") (pintype "passive"))
      (node (ref "LED23") (pin "C") (pinfunction "C_C") (pintype "passive"))
      (node (ref "LED24") (pin "C") (pinfunction "C_C") (pintype "passive"))
      (node (ref "LEDM_IC_A") (pin "6") (pinfunction "DIG2_6") (pintype "output"))
    )
    (net (code "27") (name "Net-(LEDM_IC_A-DIG3)") (class "Default")
      (node (ref "LED25") (pin "C") (pinfunction "C_C") (pintype "passive"))
      (node (ref "LED26") (pin "C") (pinfunction "C_C") (pintype "passive"))
      (node (ref "LED27") (pin "C") (pinfunction "C_C") (pintype "passive"))
      (node (ref "LED28") (pin "C") (pinfunction "C_C") (pintype "passive"))
      (node (ref "LED29") (pin "C") (pinfunction "C_C") (pintype "passive"))
      (node (ref "LED30") (pin "C") (pinfunction "C_C") (pintype "passive"))
      (node (ref "LED31") (pin "C") (pinfunction "C_C") (pintype "passive"))
      (node (ref "LED32") (pin "C") (pinfunction "C_C") (pintype "passive"))
      (node (ref "LEDM_IC_A") (pin "7") (pinfunction "DIG3_7") (pintype "output"))
    )
    (net (code "28") (name "Net-(LEDM_IC_A-DIG4)") (class "Default")
      (node (ref "LED33") (pin "C") (pinfunction "C_C") (pintype "passive"))
      (node (ref "LED34") (pin "C") (pinfunction "C_C") (pintype "passive"))
      (node (ref "LED35") (pin "C") (pinfunction "C_C") (pintype "passive"))
      (node (ref "LED36") (pin "C") (pinfunction "C_C") (pintype "passive"))
      (node (ref "LED37") (pin "C") (pinfunction "C_C") (pintype "passive"))
      (node (ref "LED38") (pin "C") (pinfunction "C_C") (pintype "passive"))
      (node (ref "LED39") (pin "C") (pinfunction "C_C") (pintype "passive"))
      (node (ref "LED40") (pin "C") (pinfunction "C_C") (pintype "passive"))
      (node (ref "LEDM_IC_A") (pin "3") (pinfunction "DIG4_3") (pintype "output"))
    )
    (net (code "29") (name "Net-(LEDM_IC_A-DIG5)") (class "Default")
      (node (ref "LED41") (pin "C") (pinfunction "C_C") (pintype "passive"))
      (node (ref "LED42") (pin "C") (pinfunction "C_C") (pintype "passive"))
      (node (ref "LED43") (pin "C") (pinfunction "C_C") (pintype "passive"))
      (node (ref "LED44") (pin "C") (pinfunction "C_C") (pintype "passive"))
      (node (ref "LED45") (pin "C") (pinfunction "C_C") (pintype "passive"))
      (node (ref "LED46") (pin "C") (pinfunction "C_C") (pintype "passive"))
      (node (ref "LED47") (pin "C") (pinfunction "C_C") (pintype "passive"))
      (node (ref "LED48") (pin "C") (pinfunction "C_C") (pintype "passive"))
      (node (ref "LEDM_IC_A") (pin "10") (pinfunction "DIG5_10") (pintype "output"))
    )
    (net (code "30") (name "Net-(LEDM_IC_A-DIG6)") (class "Default")
      (node (ref "LED49") (pin "C") (pinfunction "C_C") (pintype "passive"))
      (node (ref "LED50") (pin "C") (pinfunction "C_C") (pintype "passive"))
      (node (ref "LED51") (pin "C") (pinfunction "C_C") (pintype "passive"))
      (node (ref "LED52") (pin "C") (pinfunction "C_C") (pintype "passive"))
      (node (ref "LED53") (pin "C") (pinfunction "C_C") (pintype "passive"))
      (node (ref "LED54") (pin "C") (pinfunction "C_C") (pintype "passive"))
      (node (ref "LED55") (pin "C") (pinfunction "C_C") (pintype "passive"))
      (node (ref "LED56") (pin "C") (pinfunction "C_C") (pintype "passive"))
      (node (ref "LEDM_IC_A") (pin "5") (pinfunction "DIG6_5") (pintype "output"))
    )
    (net (code "31") (name "Net-(LEDM_IC_A-DIG7)") (class "Default")
      (node (ref "LED57") (pin "C") (pinfunction "C_C") (pintype "passive"))
      (node (ref "LED58") (pin "C") (pinfunction "C_C") (pintype "passive"))
      (node (ref "LED59") (pin "C") (pinfunction "C_C") (pintype "passive"))
      (node (ref "LED60") (pin "C") (pinfunction "C_C") (pintype "passive"))
      (node (ref "LED61") (pin "C") (pinfunction "C_C") (pintype "passive"))
      (node (ref "LED62") (pin "C") (pinfunction "C_C") (pintype "passive"))
      (node (ref "LED63") (pin "C") (pinfunction "C_C") (pintype "passive"))
      (node (ref "LED64") (pin "C") (pinfunction "C_C") (pintype "passive"))
      (node (ref "LEDM_IC_A") (pin "8") (pinfunction "DIG7_8") (pintype "output"))
    )
    (net (code "32") (name "Net-(LEDM_IC_A-ISET)") (class "Default")
      (node (ref "LEDM_IC_A") (pin "18") (pinfunction "ISET_18") (pintype "input"))
      (node (ref "R7") (pin "2") (pinfunction "2_2") (pintype "passive"))
    )
    (net (code "33") (name "Net-(LEDM_IC_A-SEGA)") (class "Default")
      (node (ref "LED10") (pin "A") (pinfunction "A_A") (pintype "passive"))
      (node (ref "LED18") (pin "A") (pinfunction "A_A") (pintype "passive"))
      (node (ref "LED2") (pin "A") (pinfunction "A_A") (pintype "passive"))
      (node (ref "LED26") (pin "A") (pinfunction "A_A") (pintype "passive"))
      (node (ref "LED34") (pin "A") (pinfunction "A_A") (pintype "passive"))
      (node (ref "LED42") (pin "A") (pinfunction "A_A") (pintype "passive"))
      (node (ref "LED50") (pin "A") (pinfunction "A_A") (pintype "passive"))
      (node (ref "LED58") (pin "A") (pinfunction "A_A") (pintype "passive"))
      (node (ref "LEDM_IC_A") (pin "14") (pinfunction "SEGA_14") (pintype "output"))
    )
    (net (code "34") (name "Net-(LEDM_IC_A-SEGB)") (class "Default")
      (node (ref "LED11") (pin "A") (pinfunction "A_A") (pintype "passive"))
      (node (ref "LED19") (pin "A") (pinfunction "A_A") (pintype "passive"))
      (node (ref "LED27") (pin "A") (pinfunction "A_A") (pintype "passive"))
      (node (ref "LED3") (pin "A") (pinfunction "A_A") (pintype "passive"))
      (node (ref "LED35") (pin "A") (pinfunction "A_A") (pintype "passive"))
      (node (ref "LED43") (pin "A") (pinfunction "A_A") (pintype "passive"))
      (node (ref "LED51") (pin "A") (pinfunction "A_A") (pintype "passive"))
      (node (ref "LED59") (pin "A") (pinfunction "A_A") (pintype "passive"))
      (node (ref "LEDM_IC_A") (pin "16") (pinfunction "SEGB_16") (pintype "output"))
    )
    (net (code "35") (name "Net-(LEDM_IC_A-SEGC)") (class "Default")
      (node (ref "LED12") (pin "A") (pinfunction "A_A") (pintype "passive"))
      (node (ref "LED20") (pin "A") (pinfunction "A_A") (pintype "passive"))
      (node (ref "LED28") (pin "A") (pinfunction "A_A") (pintype "passive"))
      (node (ref "LED36") (pin "A") (pinfunction "A_A") (pintype "passive"))
      (node (ref "LED4") (pin "A") (pinfunction "A_A") (pintype "passive"))
      (node (ref "LED44") (pin "A") (pinfunction "A_A") (pintype "passive"))
      (node (ref "LED52") (pin "A") (pinfunction "A_A") (pintype "passive"))
      (node (ref "LED60") (pin "A") (pinfunction "A_A") (pintype "passive"))
      (node (ref "LEDM_IC_A") (pin "20") (pinfunction "SEGC_20") (pintype "output"))
    )
    (net (code "36") (name "Net-(LEDM_IC_A-SEGD)") (class "Default")
      (node (ref "LED13") (pin "A") (pinfunction "A_A") (pintype "passive"))
      (node (ref "LED21") (pin "A") (pinfunction "A_A") (pintype "passive"))
      (node (ref "LED29") (pin "A") (pinfunction "A_A") (pintype "passive"))
      (node (ref "LED37") (pin "A") (pinfunction "A_A") (pintype "passive"))
      (node (ref "LED45") (pin "A") (pinfunction "A_A") (pintype "passive"))
      (node (ref "LED5") (pin "A") (pinfunction "A_A") (pintype "passive"))
      (node (ref "LED53") (pin "A") (pinfunction "A_A") (pintype "passive"))
      (node (ref "LED61") (pin "A") (pinfunction "A_A") (pintype "passive"))
      (node (ref "LEDM_IC_A") (pin "23") (pinfunction "SEGD_23") (pintype "output"))
    )
    (net (code "37") (name "Net-(LEDM_IC_A-SEGDP)") (class "Default")
      (node (ref "LED1") (pin "A") (pinfunction "A_A") (pintype "passive"))
      (node (ref "LED17") (pin "A") (pinfunction "A_A") (pintype "passive"))
      (node (ref "LED25") (pin "A") (pinfunction "A_A") (pintype "passive"))
      (node (ref "LED33") (pin "A") (pinfunction "A_A") (pintype "passive"))
      (node (ref "LED41") (pin "A") (pinfunction "A_A") (pintype "passive"))
      (node (ref "LED49") (pin "A") (pinfunction "A_A") (pintype "passive"))
      (node (ref "LED57") (pin "A") (pinfunction "A_A") (pintype "passive"))
      (node (ref "LED9") (pin "A") (pinfunction "A_A") (pintype "passive"))
      (node (ref "LEDM_IC_A") (pin "22") (pinfunction "SEGDP_22") (pintype "output"))
    )
    (net (code "38") (name "Net-(LEDM_IC_A-SEGE)") (class "Default")
      (node (ref "LED14") (pin "A") (pinfunction "A_A") (pintype "passive"))
      (node (ref "LED22") (pin "A") (pinfunction "A_A") (pintype "passive"))
      (node (ref "LED30") (pin "A") (pinfunction "A_A") (pintype "passive"))
      (node (ref "LED38") (pin "A") (pinfunction "A_A") (pintype "passive"))
      (node (ref "LED46") (pin "A") (pinfunction "A_A") (pintype "passive"))
      (node (ref "LED54") (pin "A") (pinfunction "A_A") (pintype "passive"))
      (node (ref "LED6") (pin "A") (pinfunction "A_A") (pintype "passive"))
      (node (ref "LED62") (pin "A") (pinfunction "A_A") (pintype "passive"))
      (node (ref "LEDM_IC_A") (pin "21") (pinfunction "SEGE_21") (pintype "output"))
    )
    (net (code "39") (name "Net-(LEDM_IC_A-SEGF)") (class "Default")
      (node (ref "LED15") (pin "A") (pinfunction "A_A") (pintype "passive"))
      (node (ref "LED23") (pin "A") (pinfunction "A_A") (pintype "passive"))
      (node (ref "LED31") (pin "A") (pinfunction "A_A") (pintype "passive"))
      (node (ref "LED39") (pin "A") (pinfunction "A_A") (pintype "passive"))
      (node (ref "LED47") (pin "A") (pinfunction "A_A") (pintype "passive"))
      (node (ref "LED55") (pin "A") (pinfunction "A_A") (pintype "passive"))
      (node (ref "LED63") (pin "A") (pinfunction "A_A") (pintype "passive"))
      (node (ref "LED7") (pin "A") (pinfunction "A_A") (pintype "passive"))
      (node (ref "LEDM_IC_A") (pin "15") (pinfunction "SEGF_15") (pintype "output"))
    )
    (net (code "40") (name "Net-(LEDM_IC_A-SEGG)") (class "Default")
      (node (ref "LED16") (pin "A") (pinfunction "A_A") (pintype "passive"))
      (node (ref "LED24") (pin "A") (pinfunction "A_A") (pintype "passive"))
      (node (ref "LED32") (pin "A") (pinfunction "A_A") (pintype "passive"))
      (node (ref "LED40") (pin "A") (pinfunction "A_A") (pintype "passive"))
      (node (ref "LED48") (pin "A") (pinfunction "A_A") (pintype "passive"))
      (node (ref "LED56") (pin "A") (pinfunction "A_A") (pintype "passive"))
      (node (ref "LED64") (pin "A") (pinfunction "A_A") (pintype "passive"))
      (node (ref "LED8") (pin "A") (pinfunction "A_A") (pintype "passive"))
      (node (ref "LEDM_IC_A") (pin "17") (pinfunction "SEGG_17") (pintype "output"))
    )
    (net (code "41") (name "Net-(LEDM_IC_B-DIG0)") (class "Default")
      (node (ref "LED65") (pin "C") (pinfunction "C_C") (pintype "passive"))
      (node (ref "LED66") (pin "C") (pinfunction "C_C") (pintype "passive"))
      (node (ref "LED67") (pin "C") (pinfunction "C_C") (pintype "passive"))
      (node (ref "LED68") (pin "C") (pinfunction "C_C") (pintype "passive"))
      (node (ref "LED69") (pin "C") (pinfunction "C_C") (pintype "passive"))
      (node (ref "LED70") (pin "C") (pinfunction "C_C") (pintype "passive"))
      (node (ref "LED71") (pin "C") (pinfunction "C_C") (pintype "passive"))
      (node (ref "LED72") (pin "C") (pinfunction "C_C") (pintype "passive"))
      (node (ref "LEDM_IC_B") (pin "2") (pinfunction "DIG0_2") (pintype "output"))
    )
    (net (code "42") (name "Net-(LEDM_IC_B-DIG1)") (class "Default")
      (node (ref "LED73") (pin "C") (pinfunction "C_C") (pintype "passive"))
      (node (ref "LED74") (pin "C") (pinfunction "C_C") (pintype "passive"))
      (node (ref "LED75") (pin "C") (pinfunction "C_C") (pintype "passive"))
      (node (ref "LED76") (pin "C") (pinfunction "C_C") (pintype "passive"))
      (node (ref "LED77") (pin "C") (pinfunction "C_C") (pintype "passive"))
      (node (ref "LED78") (pin "C") (pinfunction "C_C") (pintype "passive"))
      (node (ref "LED79") (pin "C") (pinfunction "C_C") (pintype "passive"))
      (node (ref "LED80") (pin "C") (pinfunction "C_C") (pintype "passive"))
      (node (ref "LEDM_IC_B") (pin "11") (pinfunction "DIG1_11") (pintype "output"))
    )
    (net (code "43") (name "Net-(LEDM_IC_B-DIG2)") (class "Default")
      (node (ref "LED81") (pin "C") (pinfunction "C_C") (pintype "passive"))
      (node (ref "LED82") (pin "C") (pinfunction "C_C") (pintype "passive"))
      (node (ref "LED83") (pin "C") (pinfunction "C_C") (pintype "passive"))
      (node (ref "LED84") (pin "C") (pinfunction "C_C") (pintype "passive"))
      (node (ref "LED85") (pin "C") (pinfunction "C_C") (pintype "passive"))
      (node (ref "LED86") (pin "C") (pinfunction "C_C") (pintype "passive"))
      (node (ref "LED87") (pin "C") (pinfunction "C_C") (pintype "passive"))
      (node (ref "LED88") (pin "C") (pinfunction "C_C") (pintype "passive"))
      (node (ref "LEDM_IC_B") (pin "6") (pinfunction "DIG2_6") (pintype "output"))
    )
    (net (code "44") (name "Net-(LEDM_IC_B-DIG3)") (class "Default")
      (node (ref "LED89") (pin "C") (pinfunction "C_C") (pintype "passive"))
      (node (ref "LED90") (pin "C") (pinfunction "C_C") (pintype "passive"))
      (node (ref "LED91") (pin "C") (pinfunction "C_C") (pintype "passive"))
      (node (ref "LED92") (pin "C") (pinfunction "C_C") (pintype "passive"))
      (node (ref "LED93") (pin "C") (pinfunction "C_C") (pintype "passive"))
      (node (ref "LED94") (pin "C") (pinfunction "C_C") (pintype "passive"))
      (node (ref "LED95") (pin "C") (pinfunction "C_C") (pintype "passive"))
      (node (ref "LED96") (pin "C") (pinfunction "C_C") (pintype "passive"))
      (node (ref "LEDM_IC_B") (pin "7") (pinfunction "DIG3_7") (pintype "output"))
    )
    (net (code "45") (name "Net-(LEDM_IC_B-DIG4)") (class "Default")
      (node (ref "LED100") (pin "C") (pinfunction "C_C") (pintype "passive"))
      (node (ref "LED101") (pin "C") (pinfunction "C_C") (pintype "passive"))
      (node (ref "LED102") (pin "C") (pinfunction "C_C") (pintype "passive"))
      (node (ref "LED103") (pin "C") (pinfunction "C_C") (pintype "passive"))
      (node (ref "LED104") (pin "C") (pinfunction "C_C") (pintype "passive"))
      (node (ref "LED97") (pin "C") (pinfunction "C_C") (pintype "passive"))
      (node (ref "LED98") (pin "C") (pinfunction "C_C") (pintype "passive"))
      (node (ref "LED99") (pin "C") (pinfunction "C_C") (pintype "passive"))
      (node (ref "LEDM_IC_B") (pin "3") (pinfunction "DIG4_3") (pintype "output"))
    )
    (net (code "46") (name "Net-(LEDM_IC_B-DIG5)") (class "Default")
      (node (ref "LED105") (pin "C") (pinfunction "C_C") (pintype "passive"))
      (node (ref "LED106") (pin "C") (pinfunction "C_C") (pintype "passive"))
      (node (ref "LED107") (pin "C") (pinfunction "C_C") (pintype "passive"))
      (node (ref "LED108") (pin "C") (pinfunction "C_C") (pintype "passive"))
      (node (ref "LED109") (pin "C") (pinfunction "C_C") (pintype "passive"))
      (node (ref "LED110") (pin "C") (pinfunction "C_C") (pintype "passive"))
      (node (ref "LED111") (pin "C") (pinfunction "C_C") (pintype "passive"))
      (node (ref "LED112") (pin "C") (pinfunction "C_C") (pintype "passive"))
      (node (ref "LEDM_IC_B") (pin "10") (pinfunction "DIG5_10") (pintype "output"))
    )
    (net (code "47") (name "Net-(LEDM_IC_B-DIG6)") (class "Default")
      (node (ref "LED113") (pin "C") (pinfunction "C_C") (pintype "passive"))
      (node (ref "LED114") (pin "C") (pinfunction "C_C") (pintype "passive"))
      (node (ref "LED115") (pin "C") (pinfunction "C_C") (pintype "passive"))
      (node (ref "LED116") (pin "C") (pinfunction "C_C") (pintype "passive"))
      (node (ref "LED117") (pin "C") (pinfunction "C_C") (pintype "passive"))
      (node (ref "LED118") (pin "C") (pinfunction "C_C") (pintype "passive"))
      (node (ref "LED119") (pin "C") (pinfunction "C_C") (pintype "passive"))
      (node (ref "LED120") (pin "C") (pinfunction "C_C") (pintype "passive"))
      (node (ref "LEDM_IC_B") (pin "5") (pinfunction "DIG6_5") (pintype "output"))
    )
    (net (code "48") (name "Net-(LEDM_IC_B-DIG7)") (class "Default")
      (node (ref "LED121") (pin "C") (pinfunction "C_C") (pintype "passive"))
      (node (ref "LED122") (pin "C") (pinfunction "C_C") (pintype "passive"))
      (node (ref "LED123") (pin "C") (pinfunction "C_C") (pintype "passive"))
      (node (ref "LED124") (pin "C") (pinfunction "C_C") (pintype "passive"))
      (node (ref "LED125") (pin "C") (pinfunction "C_C") (pintype "passive"))
      (node (ref "LED126") (pin "C") (pinfunction "C_C") (pintype "passive"))
      (node (ref "LED127") (pin "C") (pinfunction "C_C") (pintype "passive"))
      (node (ref "LED128") (pin "C") (pinfunction "C_C") (pintype "passive"))
      (node (ref "LEDM_IC_B") (pin "8") (pinfunction "DIG7_8") (pintype "output"))
    )
    (net (code "49") (name "Net-(LEDM_IC_B-ISET)") (class "Default")
      (node (ref "LEDM_IC_B") (pin "18") (pinfunction "ISET_18") (pintype "input"))
      (node (ref "R8") (pin "2") (pinfunction "2_2") (pintype "passive"))
    )
    (net (code "50") (name "Net-(LEDM_IC_B-SEGA)") (class "Default")
      (node (ref "LED106") (pin "A") (pinfunction "A_A") (pintype "passive"))
      (node (ref "LED114") (pin "A") (pinfunction "A_A") (pintype "passive"))
      (node (ref "LED122") (pin "A") (pinfunction "A_A") (pintype "passive"))
      (node (ref "LED66") (pin "A") (pinfunction "A_A") (pintype "passive"))
      (node (ref "LED74") (pin "A") (pinfunction "A_A") (pintype "passive"))
      (node (ref "LED82") (pin "A") (pinfunction "A_A") (pintype "passive"))
      (node (ref "LED90") (pin "A") (pinfunction "A_A") (pintype "passive"))
      (node (ref "LED98") (pin "A") (pinfunction "A_A") (pintype "passive"))
      (node (ref "LEDM_IC_B") (pin "14") (pinfunction "SEGA_14") (pintype "output"))
    )
    (net (code "51") (name "Net-(LEDM_IC_B-SEGB)") (class "Default")
      (node (ref "LED107") (pin "A") (pinfunction "A_A") (pintype "passive"))
      (node (ref "LED115") (pin "A") (pinfunction "A_A") (pintype "passive"))
      (node (ref "LED123") (pin "A") (pinfunction "A_A") (pintype "passive"))
      (node (ref "LED67") (pin "A") (pinfunction "A_A") (pintype "passive"))
      (node (ref "LED75") (pin "A") (pinfunction "A_A") (pintype "passive"))
      (node (ref "LED83") (pin "A") (pinfunction "A_A") (pintype "passive"))
      (node (ref "LED91") (pin "A") (pinfunction "A_A") (pintype "passive"))
      (node (ref "LED99") (pin "A") (pinfunction "A_A") (pintype "passive"))
      (node (ref "LEDM_IC_B") (pin "16") (pinfunction "SEGB_16") (pintype "output"))
    )
    (net (code "52") (name "Net-(LEDM_IC_B-SEGC)") (class "Default")
      (node (ref "LED100") (pin "A") (pinfunction "A_A") (pintype "passive"))
      (node (ref "LED108") (pin "A") (pinfunction "A_A") (pintype "passive"))
      (node (ref "LED116") (pin "A") (pinfunction "A_A") (pintype "passive"))
      (node (ref "LED124") (pin "A") (pinfunction "A_A") (pintype "passive"))
      (node (ref "LED68") (pin "A") (pinfunction "A_A") (pintype "passive"))
      (node (ref "LED76") (pin "A") (pinfunction "A_A") (pintype "passive"))
      (node (ref "LED84") (pin "A") (pinfunction "A_A") (pintype "passive"))
      (node (ref "LED92") (pin "A") (pinfunction "A_A") (pintype "passive"))
      (node (ref "LEDM_IC_B") (pin "20") (pinfunction "SEGC_20") (pintype "output"))
    )
    (net (code "53") (name "Net-(LEDM_IC_B-SEGD)") (class "Default")
      (node (ref "LED101") (pin "A") (pinfunction "A_A") (pintype "passive"))
      (node (ref "LED109") (pin "A") (pinfunction "A_A") (pintype "passive"))
      (node (ref "LED117") (pin "A") (pinfunction "A_A") (pintype "passive"))
      (node (ref "LED125") (pin "A") (pinfunction "A_A") (pintype "passive"))
      (node (ref "LED69") (pin "A") (pinfunction "A_A") (pintype "passive"))
      (node (ref "LED77") (pin "A") (pinfunction "A_A") (pintype "passive"))
      (node (ref "LED85") (pin "A") (pinfunction "A_A") (pintype "passive"))
      (node (ref "LED93") (pin "A") (pinfunction "A_A") (pintype "passive"))
      (node (ref "LEDM_IC_B") (pin "23") (pinfunction "SEGD_23") (pintype "output"))
    )
    (net (code "54") (name "Net-(LEDM_IC_B-SEGDP)") (class "Default")
      (node (ref "LED105") (pin "A") (pinfunction "A_A") (pintype "passive"))
      (node (ref "LED113") (pin "A") (pinfunction "A_A") (pintype "passive"))
      (node (ref "LED121") (pin "A") (pinfunction "A_A") (pintype "passive"))
      (node (ref "LED65") (pin "A") (pinfunction "A_A") (pintype "passive"))
      (node (ref "LED73") (pin "A") (pinfunction "A_A") (pintype "passive"))
      (node (ref "LED81") (pin "A") (pinfunction "A_A") (pintype "passive"))
      (node (ref "LED89") (pin "A") (pinfunction "A_A") (pintype "passive"))
      (node (ref "LED97") (pin "A") (pinfunction "A_A") (pintype "passive"))
      (node (ref "LEDM_IC_B") (pin "22") (pinfunction "SEGDP_22") (pintype "output"))
    )
    (net (code "55") (name "Net-(LEDM_IC_B-SEGE)") (class "Default")
      (node (ref "LED102") (pin "A") (pinfunction "A_A") (pintype "passive"))
      (node (ref "LED110") (pin "A") (pinfunction "A_A") (pintype "passive"))
      (node (ref "LED118") (pin "A") (pinfunction "A_A") (pintype "passive"))
      (node (ref "LED126") (pin "A") (pinfunction "A_A") (pintype "passive"))
      (node (ref "LED70") (pin "A") (pinfunction "A_A") (pintype "passive"))
      (node (ref "LED78") (pin "A") (pinfunction "A_A") (pintype "passive"))
      (node (ref "LED86") (pin "A") (pinfunction "A_A") (pintype "passive"))
      (node (ref "LED94") (pin "A") (pinfunction "A_A") (pintype "passive"))
      (node (ref "LEDM_IC_B") (pin "21") (pinfunction "SEGE_21") (pintype "output"))
    )
    (net (code "56") (name "Net-(LEDM_IC_B-SEGF)") (class "Default")
      (node (ref "LED103") (pin "A") (pinfunction "A_A") (pintype "passive"))
      (node (ref "LED111") (pin "A") (pinfunction "A_A") (pintype "passive"))
      (node (ref "LED119") (pin "A") (pinfunction "A_A") (pintype "passive"))
      (node (ref "LED127") (pin "A") (pinfunction "A_A") (pintype "passive"))
      (node (ref "LED71") (pin "A") (pinfunction "A_A") (pintype "passive"))
      (node (ref "LED79") (pin "A") (pinfunction "A_A") (pintype "passive"))
      (node (ref "LED87") (pin "A") (pinfunction "A_A") (pintype "passive"))
      (node (ref "LED95") (pin "A") (pinfunction "A_A") (pintype "passive"))
      (node (ref "LEDM_IC_B") (pin "15") (pinfunction "SEGF_15") (pintype "output"))
    )
    (net (code "57") (name "Net-(LEDM_IC_B-SEGG)") (class "Default")
      (node (ref "LED104") (pin "A") (pinfunction "A_A") (pintype "passive"))
      (node (ref "LED112") (pin "A") (pinfunction "A_A") (pintype "passive"))
      (node (ref "LED120") (pin "A") (pinfunction "A_A") (pintype "passive"))
      (node (ref "LED128") (pin "A") (pinfunction "A_A") (pintype "passive"))
      (node (ref "LED72") (pin "A") (pinfunction "A_A") (pintype "passive"))
      (node (ref "LED80") (pin "A") (pinfunction "A_A") (pintype "passive"))
      (node (ref "LED88") (pin "A") (pinfunction "A_A") (pintype "passive"))
      (node (ref "LED96") (pin "A") (pinfunction "A_A") (pintype "passive"))
      (node (ref "LEDM_IC_B") (pin "17") (pinfunction "SEGG_17") (pintype "output"))
    )
    (net (code "58") (name "VCC") (class "Default")
      (node (ref "ARDUINO") (pin "5V") (pinfunction "5V_5V") (pintype "bidirectional"))
      (node (ref "A_ENTER") (pin "1") (pinfunction "S_1") (pintype "passive"))
      (node (ref "A_LEFT") (pin "1") (pinfunction "S_1") (pintype "passive"))
      (node (ref "A_RIGHT") (pin "1") (pinfunction "S_1") (pintype "passive"))
      (node (ref "B_ENTER") (pin "1") (pinfunction "S_1") (pintype "passive"))
      (node (ref "B_LEFT") (pin "1") (pinfunction "S_1") (pintype "passive"))
      (node (ref "B_RIGHT") (pin "1") (pinfunction "S_1") (pintype "passive"))
      (node (ref "C7") (pin "1") (pinfunction "1_1") (pintype "passive"))
      (node (ref "C8") (pin "1") (pinfunction "1_1") (pintype "passive"))
      (node (ref "LEDM_IC_A") (pin "19") (pinfunction "VCC_19") (pintype "power_in"))
      (node (ref "LEDM_IC_B") (pin "19") (pinfunction "VCC_19") (pintype "power_in"))
      (node (ref "R7") (pin "1") (pinfunction "1_1") (pintype "passive"))
      (node (ref "R8") (pin "1") (pinfunction "1_1") (pintype "passive"))
    )
    (net (code "59") (name "unconnected-(ARDUINO-*D3-PadD3)") (class "Default")
      (node (ref "ARDUINO") (pin "D3") (pinfunction "*D3_D3") (pintype "bidirectional"))
    )
    (net (code "60") (name "unconnected-(ARDUINO-GND-PadGND@1)") (class "Default")
      (node (ref "ARDUINO") (pin "GND@1") (pinfunction "GND_GND@1") (pintype "bidirectional"))
    )
    (net (code "61") (name "unconnected-(ARDUINO-GND-PadGND@3)") (class "Default")
      (node (ref "ARDUINO") (pin "GND@3") (pinfunction "GND_GND@3") (pintype "bidirectional"))
    )
    (net (code "62") (name "unconnected-(ARDUINO-GND-PadGND@4)") (class "Default")
      (node (ref "ARDUINO") (pin "GND@4") (pinfunction "GND_GND@4") (pintype "bidirectional"))
    )
    (net (code "63") (name "unconnected-(ARDUINO-Pad3.3V)") (class "Default")
      (node (ref "ARDUINO") (pin "3.3V") (pinfunction "3.3V_3.3V") (pintype "bidirectional"))
    )
    (net (code "64") (name "unconnected-(ARDUINO-PadA0)") (class "Default")
      (node (ref "ARDUINO") (pin "A0") (pinfunction "A0_A0") (pintype "bidirectional"))
    )
    (net (code "65") (name "unconnected-(ARDUINO-PadA1)") (class "Default")
      (node (ref "ARDUINO") (pin "A1") (pinfunction "A1_A1") (pintype "bidirectional"))
    )
    (net (code "66") (name "unconnected-(ARDUINO-PadA2)") (class "Default")
      (node (ref "ARDUINO") (pin "A2") (pinfunction "A2_A2") (pintype "bidirectional"))
    )
    (net (code "67") (name "unconnected-(ARDUINO-PadA3)") (class "Default")
      (node (ref "ARDUINO") (pin "A3") (pinfunction "A3_A3") (pintype "bidirectional"))
    )
    (net (code "68") (name "unconnected-(ARDUINO-PadA4)") (class "Default")
      (node (ref "ARDUINO") (pin "A4") (pinfunction "A4_A4") (pintype "bidirectional"))
    )
    (net (code "69") (name "unconnected-(ARDUINO-PadA5)") (class "Default")
      (node (ref "ARDUINO") (pin "A5") (pinfunction "A5_A5") (pintype "bidirectional"))
    )
    (net (code "70") (name "unconnected-(ARDUINO-PadAREF)") (class "Default")
      (node (ref "ARDUINO") (pin "AREF") (pinfunction "AREF_AREF") (pintype "bidirectional"))
    )
    (net (code "71") (name "unconnected-(ARDUINO-PadD0)") (class "Default")
      (node (ref "ARDUINO") (pin "D0") (pinfunction "D0_D0") (pintype "bidirectional"))
    )
    (net (code "72") (name "unconnected-(ARDUINO-PadD1)") (class "Default")
      (node (ref "ARDUINO") (pin "D1") (pinfunction "D1_D1") (pintype "bidirectional"))
    )
    (net (code "73") (name "unconnected-(ARDUINO-PadD12)") (class "Default")
      (node (ref "ARDUINO") (pin "D12") (pinfunction "D12_D12") (pintype "bidirectional"))
    )
    (net (code "74") (name "unconnected-(ARDUINO-PadIOREF)") (class "Default")
      (node (ref "ARDUINO") (pin "IOREF") (pinfunction "IOREF_IOREF") (pintype "bidirectional"))
    )
    (net (code "75") (name "unconnected-(ARDUINO-PadMISO)") (class "Default")
      (node (ref "ARDUINO") (pin "MISO") (pinfunction "MISO_MISO") (pintype "bidirectional"))
    )
    (net (code "76") (name "unconnected-(ARDUINO-PadMOSI)") (class "Default")
      (node (ref "ARDUINO") (pin "MOSI") (pinfunction "MOSI_MOSI") (pintype "bidirectional"))
    )
    (net (code "77") (name "unconnected-(ARDUINO-PadSCK)") (class "Default")
      (node (ref "ARDUINO") (pin "SCK") (pinfunction "SCK_SCK") (pintype "bidirectional"))
    )
    (net (code "78") (name "unconnected-(ARDUINO-PadSCL)") (class "Default")
      (node (ref "ARDUINO") (pin "SCL") (pinfunction "SCL_SCL") (pintype "bidirectional"))
    )
    (net (code "79") (name "unconnected-(ARDUINO-PadSDA)") (class "Default")
      (node (ref "ARDUINO") (pin "SDA") (pinfunction "SDA_SDA") (pintype "bidirectional"))
    )
    (net (code "80") (name "unconnected-(ARDUINO-PadVCC)") (class "Default")
      (node (ref "ARDUINO") (pin "VCC") (pinfunction "VCC_VCC") (pintype "bidirectional"))
    )
    (net (code "81") (name "unconnected-(ARDUINO-PadVIN)") (class "Default")
      (node (ref "ARDUINO") (pin "VIN") (pinfunction "VIN_VIN") (pintype "bidirectional"))
    )
    (net (code "82") (name "unconnected-(ARDUINO-~{RESET}-PadRESET@1)") (class "Default")
      (node (ref "ARDUINO") (pin "RESET@1") (pinfunction "~{RESET}_RESET@1") (pintype "bidirectional"))
    )
    (net (code "83") (name "unconnected-(ARDUINO-~{RESET}-PadRESET@2)") (class "Default")
      (node (ref "ARDUINO") (pin "RESET@2") (pinfunction "~{RESET}_RESET@2") (pintype "bidirectional"))
    )
    (net (code "84") (name "unconnected-(LEDM_IC_A-DOUT-Pad24)") (class "Default")
      (node (ref "LEDM_IC_A") (pin "24") (pinfunction "DOUT_24") (pintype "output"))
    )
    (net (code "85") (name "unconnected-(LEDM_IC_B-DOUT-Pad24)") (class "Default")
      (node (ref "LEDM_IC_B") (pin "24") (pinfunction "DOUT_24") (pintype "output"))
    )
  )
)
